# lpcdev.net
KiCad netlist of a schematic drawn in EAGLE
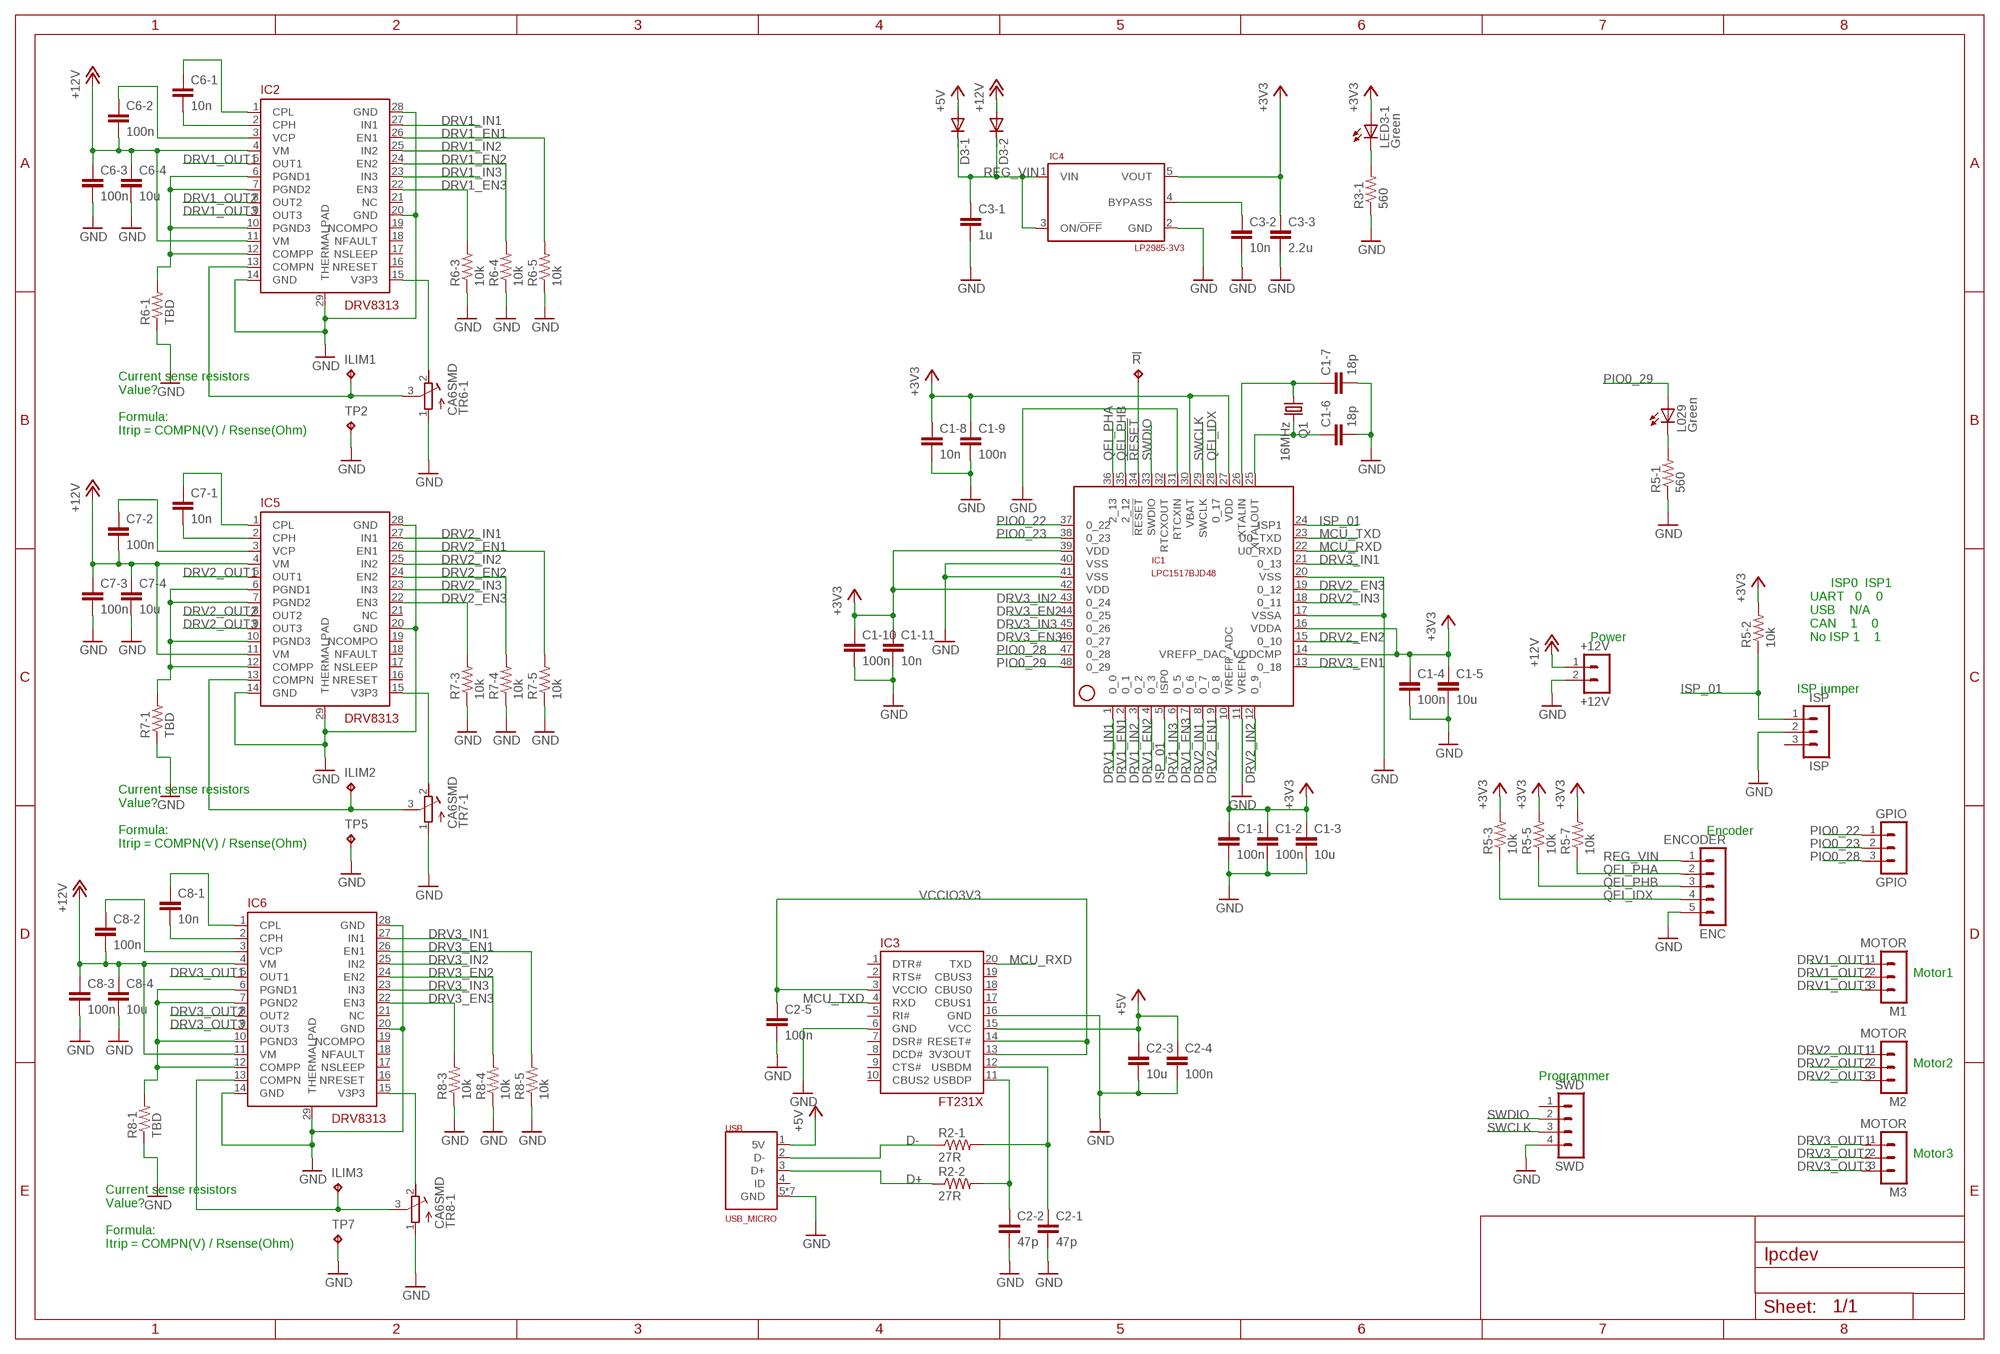
[diagram p0: schematic, sheet 1]

(export (version "E")
  (design (tool "Eeschema 10.0.6"))
  (components
    (comp (ref "!R")
      (value "TPB1,27")
      (footprint "eagle-import:B1,27")
      (libsource (lib "eagle-import") (part "TPB1,27"))
    )
    (comp (ref "+12V")
      (value "+12V")
      (footprint "eagle-import:MA02-1")
      (libsource (lib "eagle-import") (part "MA02-1"))
    )
    (comp (ref "C1-1")
      (value "100n")
      (footprint "eagle-import:C0603")
      (libsource (lib "eagle-import") (part "C-EUC0603"))
    )
    (comp (ref "C1-2")
      (value "100n")
      (footprint "eagle-import:C0603")
      (libsource (lib "eagle-import") (part "C-EUC0603"))
    )
    (comp (ref "C1-3")
      (value "10u")
      (footprint "eagle-import:C0805")
      (libsource (lib "eagle-import") (part "C-EUC0805"))
    )
    (comp (ref "C1-4")
      (value "100n")
      (footprint "eagle-import:C0603")
      (libsource (lib "eagle-import") (part "C-EUC0603"))
    )
    (comp (ref "C1-5")
      (value "10u")
      (footprint "eagle-import:C0805")
      (libsource (lib "eagle-import") (part "C-EUC0805"))
    )
    (comp (ref "C1-6")
      (value "18p")
      (footprint "eagle-import:C0603")
      (libsource (lib "eagle-import") (part "C-EUC0603"))
    )
    (comp (ref "C1-7")
      (value "18p")
      (footprint "eagle-import:C0603")
      (libsource (lib "eagle-import") (part "C-EUC0603"))
    )
    (comp (ref "C1-8")
      (value "10n")
      (footprint "eagle-import:C0603")
      (libsource (lib "eagle-import") (part "C-EUC0603"))
    )
    (comp (ref "C1-9")
      (value "100n")
      (footprint "eagle-import:C0603")
      (libsource (lib "eagle-import") (part "C-EUC0603"))
    )
    (comp (ref "C1-10")
      (value "100n")
      (footprint "eagle-import:C0603")
      (libsource (lib "eagle-import") (part "C-EUC0603"))
    )
    (comp (ref "C1-11")
      (value "10n")
      (footprint "eagle-import:C0603")
      (libsource (lib "eagle-import") (part "C-EUC0603"))
    )
    (comp (ref "C2-1")
      (value "47p")
      (footprint "eagle-import:C0603")
      (libsource (lib "eagle-import") (part "C-EUC0603"))
    )
    (comp (ref "C2-2")
      (value "47p")
      (footprint "eagle-import:C0603")
      (libsource (lib "eagle-import") (part "C-EUC0603"))
    )
    (comp (ref "C2-3")
      (value "10u")
      (footprint "eagle-import:C0805")
      (libsource (lib "eagle-import") (part "C-EUC0805"))
    )
    (comp (ref "C2-4")
      (value "100n")
      (footprint "eagle-import:C0603")
      (libsource (lib "eagle-import") (part "C-EUC0603"))
    )
    (comp (ref "C2-5")
      (value "100n")
      (footprint "eagle-import:C0603")
      (libsource (lib "eagle-import") (part "C-EUC0603"))
    )
    (comp (ref "C3-1")
      (value "1u")
      (footprint "eagle-import:C0805")
      (libsource (lib "eagle-import") (part "C-EUC0805"))
    )
    (comp (ref "C3-2")
      (value "10n")
      (footprint "eagle-import:C0603")
      (libsource (lib "eagle-import") (part "C-EUC0603"))
    )
    (comp (ref "C3-3")
      (value "2.2u")
      (footprint "eagle-import:C0805")
      (libsource (lib "eagle-import") (part "C-EUC0805"))
    )
    (comp (ref "C6-1")
      (value "10n")
      (footprint "eagle-import:C0603")
      (libsource (lib "eagle-import") (part "C-EUC0603"))
    )
    (comp (ref "C6-2")
      (value "100n")
      (footprint "eagle-import:C0603")
      (libsource (lib "eagle-import") (part "C-EUC0603"))
    )
    (comp (ref "C6-3")
      (value "100n")
      (footprint "eagle-import:C0603")
      (libsource (lib "eagle-import") (part "C-EUC0603"))
    )
    (comp (ref "C6-4")
      (value "10u")
      (footprint "eagle-import:C0805")
      (libsource (lib "eagle-import") (part "C-EUC0805"))
    )
    (comp (ref "C7-1")
      (value "10n")
      (footprint "eagle-import:C0603")
      (libsource (lib "eagle-import") (part "C-EUC0603"))
    )
    (comp (ref "C7-2")
      (value "100n")
      (footprint "eagle-import:C0603")
      (libsource (lib "eagle-import") (part "C-EUC0603"))
    )
    (comp (ref "C7-3")
      (value "100n")
      (footprint "eagle-import:C0603")
      (libsource (lib "eagle-import") (part "C-EUC0603"))
    )
    (comp (ref "C7-4")
      (value "10u")
      (footprint "eagle-import:C0805")
      (libsource (lib "eagle-import") (part "C-EUC0805"))
    )
    (comp (ref "C8-1")
      (value "10n")
      (footprint "eagle-import:C0603")
      (libsource (lib "eagle-import") (part "C-EUC0603"))
    )
    (comp (ref "C8-2")
      (value "100n")
      (footprint "eagle-import:C0603")
      (libsource (lib "eagle-import") (part "C-EUC0603"))
    )
    (comp (ref "C8-3")
      (value "100n")
      (footprint "eagle-import:C0603")
      (libsource (lib "eagle-import") (part "C-EUC0603"))
    )
    (comp (ref "C8-4")
      (value "10u")
      (footprint "eagle-import:C0805")
      (libsource (lib "eagle-import") (part "C-EUC0805"))
    )
    (comp (ref "D3-1")
      (value "DIODE-SOD323-R")
      (footprint "eagle-import:SOD323-R")
      (libsource (lib "eagle-import") (part "DIODE-SOD323-R"))
    )
    (comp (ref "D3-2")
      (value "DIODE-SOD323-R")
      (footprint "eagle-import:SOD323-R")
      (libsource (lib "eagle-import") (part "DIODE-SOD323-R"))
    )
    (comp (ref "ENC")
      (value "ENCODER")
      (footprint "eagle-import:MA05-1")
      (libsource (lib "eagle-import") (part "MA05-1"))
    )
    (comp (ref "GPIO")
      (value "GPIO")
      (footprint "eagle-import:MA03-1")
      (libsource (lib "eagle-import") (part "MA03-1"))
    )
    (comp (ref "IC1")
      (value "LPC1517BJD48")
      (footprint "eagle-import:LQFP48")
      (libsource (lib "eagle-import") (part "LPC1517BJD48"))
    )
    (comp (ref "IC2")
      (value "DRV8313")
      (footprint "eagle-import:R-PDSO-G28")
      (libsource (lib "eagle-import") (part "DRV8313"))
    )
    (comp (ref "IC3")
      (value "FT231X")
      (footprint "eagle-import:SSOP-20")
      (libsource (lib "eagle-import") (part "FT231X"))
    )
    (comp (ref "IC4")
      (value "LP2985-3V3")
      (footprint "eagle-import:SOT23")
      (libsource (lib "eagle-import") (part "LP2985-3V3"))
    )
    (comp (ref "IC5")
      (value "DRV8313")
      (footprint "eagle-import:R-PDSO-G28")
      (libsource (lib "eagle-import") (part "DRV8313"))
    )
    (comp (ref "IC6")
      (value "DRV8313")
      (footprint "eagle-import:R-PDSO-G28")
      (libsource (lib "eagle-import") (part "DRV8313"))
    )
    (comp (ref "ILIM1")
      (value "TPB1,27")
      (footprint "eagle-import:B1,27")
      (libsource (lib "eagle-import") (part "TPB1,27"))
    )
    (comp (ref "ILIM2")
      (value "TPB1,27")
      (footprint "eagle-import:B1,27")
      (libsource (lib "eagle-import") (part "TPB1,27"))
    )
    (comp (ref "ILIM3")
      (value "TPB1,27")
      (footprint "eagle-import:B1,27")
      (libsource (lib "eagle-import") (part "TPB1,27"))
    )
    (comp (ref "ISP")
      (value "ISP")
      (footprint "eagle-import:MA03-1")
      (libsource (lib "eagle-import") (part "MA03-1"))
    )
    (comp (ref "L029")
      (value "Green")
      (footprint "eagle-import:CHIP-LED0603")
      (libsource (lib "eagle-import") (part "LEDCHIP-LED0603"))
    )
    (comp (ref "LED3-1")
      (value "Green")
      (footprint "eagle-import:CHIP-LED0603")
      (libsource (lib "eagle-import") (part "LEDCHIP-LED0603"))
    )
    (comp (ref "M1")
      (value "MOTOR")
      (footprint "eagle-import:MA03-1")
      (libsource (lib "eagle-import") (part "MA03-1"))
    )
    (comp (ref "M2")
      (value "MOTOR")
      (footprint "eagle-import:MA03-1")
      (libsource (lib "eagle-import") (part "MA03-1"))
    )
    (comp (ref "M3")
      (value "MOTOR")
      (footprint "eagle-import:MA03-1")
      (libsource (lib "eagle-import") (part "MA03-1"))
    )
    (comp (ref "Q1")
      (value "16MHz")
      (footprint "eagle-import:CTS406")
      (libsource (lib "eagle-import") (part "CRYSTALCTS406"))
    )
    (comp (ref "R2-1")
      (value "27R")
      (footprint "eagle-import:R0603")
      (libsource (lib "eagle-import") (part "R-US_R0603"))
    )
    (comp (ref "R2-2")
      (value "27R")
      (footprint "eagle-import:R0603")
      (libsource (lib "eagle-import") (part "R-US_R0603"))
    )
    (comp (ref "R3-1")
      (value "560")
      (footprint "eagle-import:R0603")
      (libsource (lib "eagle-import") (part "R-US_R0603"))
    )
    (comp (ref "R5-1")
      (value "560")
      (footprint "eagle-import:R0603")
      (libsource (lib "eagle-import") (part "R-US_R0603"))
    )
    (comp (ref "R5-2")
      (value "10k")
      (footprint "eagle-import:R0603")
      (libsource (lib "eagle-import") (part "R-US_R0603"))
    )
    (comp (ref "R5-3")
      (value "10k")
      (footprint "eagle-import:R0603")
      (libsource (lib "eagle-import") (part "R-US_R0603"))
    )
    (comp (ref "R5-5")
      (value "10k")
      (footprint "eagle-import:R0603")
      (libsource (lib "eagle-import") (part "R-US_R0603"))
    )
    (comp (ref "R5-7")
      (value "10k")
      (footprint "eagle-import:R0603")
      (libsource (lib "eagle-import") (part "R-US_R0603"))
    )
    (comp (ref "R6-1")
      (value "TBD")
      (footprint "eagle-import:R0805")
      (libsource (lib "eagle-import") (part "R-US_R0805"))
    )
    (comp (ref "R6-3")
      (value "10k")
      (footprint "eagle-import:R0603")
      (libsource (lib "eagle-import") (part "R-US_R0603"))
    )
    (comp (ref "R6-4")
      (value "10k")
      (footprint "eagle-import:R0603")
      (libsource (lib "eagle-import") (part "R-US_R0603"))
    )
    (comp (ref "R6-5")
      (value "10k")
      (footprint "eagle-import:R0603")
      (libsource (lib "eagle-import") (part "R-US_R0603"))
    )
    (comp (ref "R7-1")
      (value "TBD")
      (footprint "eagle-import:R0805")
      (libsource (lib "eagle-import") (part "R-US_R0805"))
    )
    (comp (ref "R7-3")
      (value "10k")
      (footprint "eagle-import:R0603")
      (libsource (lib "eagle-import") (part "R-US_R0603"))
    )
    (comp (ref "R7-4")
      (value "10k")
      (footprint "eagle-import:R0603")
      (libsource (lib "eagle-import") (part "R-US_R0603"))
    )
    (comp (ref "R7-5")
      (value "10k")
      (footprint "eagle-import:R0603")
      (libsource (lib "eagle-import") (part "R-US_R0603"))
    )
    (comp (ref "R8-1")
      (value "TBD")
      (footprint "eagle-import:R0805")
      (libsource (lib "eagle-import") (part "R-US_R0805"))
    )
    (comp (ref "R8-3")
      (value "10k")
      (footprint "eagle-import:R0603")
      (libsource (lib "eagle-import") (part "R-US_R0603"))
    )
    (comp (ref "R8-4")
      (value "10k")
      (footprint "eagle-import:R0603")
      (libsource (lib "eagle-import") (part "R-US_R0603"))
    )
    (comp (ref "R8-5")
      (value "10k")
      (footprint "eagle-import:R0603")
      (libsource (lib "eagle-import") (part "R-US_R0603"))
    )
    (comp (ref "SWD")
      (value "SWD")
      (footprint "eagle-import:MA04-1")
      (libsource (lib "eagle-import") (part "MA04-1"))
    )
    (comp (ref "TP2")
      (value "TPB1,27")
      (footprint "eagle-import:B1,27")
      (libsource (lib "eagle-import") (part "TPB1,27"))
    )
    (comp (ref "TP5")
      (value "TPB1,27")
      (footprint "eagle-import:B1,27")
      (libsource (lib "eagle-import") (part "TPB1,27"))
    )
    (comp (ref "TP7")
      (value "TPB1,27")
      (footprint "eagle-import:B1,27")
      (libsource (lib "eagle-import") (part "TPB1,27"))
    )
    (comp (ref "TR6-1")
      (value "CA6SMD")
      (footprint "eagle-import:CA6SMD")
      (libsource (lib "eagle-import") (part "CA6SMD"))
    )
    (comp (ref "TR7-1")
      (value "CA6SMD")
      (footprint "eagle-import:CA6SMD")
      (libsource (lib "eagle-import") (part "CA6SMD"))
    )
    (comp (ref "TR8-1")
      (value "CA6SMD")
      (footprint "eagle-import:CA6SMD")
      (libsource (lib "eagle-import") (part "CA6SMD"))
    )
    (comp (ref "USB")
      (value "USB_MICRO")
      (footprint "eagle-import:USB_MICRO")
      (libsource (lib "eagle-import") (part "USB_MICRO"))
    )
  )
  (nets
    (net (code "1") (name "+3V3") (class "Default")
      (node (ref "C1-1") (pin "1") (pinfunction "1_1") (pintype "passive"))
      (node (ref "C1-10") (pin "1") (pinfunction "1_1") (pintype "passive"))
      (node (ref "C1-11") (pin "1") (pinfunction "1_1") (pintype "passive"))
      (node (ref "C1-2") (pin "1") (pinfunction "1_1") (pintype "passive"))
      (node (ref "C1-3") (pin "1") (pinfunction "1_1") (pintype "passive"))
      (node (ref "C1-4") (pin "1") (pinfunction "1_1") (pintype "passive"))
      (node (ref "C1-5") (pin "1") (pinfunction "1_1") (pintype "passive"))
      (node (ref "C1-8") (pin "1") (pinfunction "1_1") (pintype "passive"))
      (node (ref "C1-9") (pin "1") (pinfunction "1_1") (pintype "passive"))
      (node (ref "C3-3") (pin "1") (pinfunction "1_1") (pintype "passive"))
      (node (ref "IC1") (pin "10") (pinfunction "VREFP_ADC_10") (pintype "power_in"))
      (node (ref "IC1") (pin "14") (pinfunction "VREFP_DAC_VDDCMP_14") (pintype "power_in"))
      (node (ref "IC1") (pin "16") (pinfunction "VDDA_16") (pintype "power_in"))
      (node (ref "IC1") (pin "27") (pinfunction "VDD_27") (pintype "power_in"))
      (node (ref "IC1") (pin "30") (pinfunction "VBAT_30") (pintype "power_in"))
      (node (ref "IC1") (pin "39") (pinfunction "VDD_39") (pintype "power_in"))
      (node (ref "IC1") (pin "42") (pinfunction "VDD_42") (pintype "power_in"))
      (node (ref "IC4") (pin "5") (pinfunction "VOUT_5") (pintype "bidirectional"))
      (node (ref "LED3-1") (pin "A") (pinfunction "A_A") (pintype "passive"))
      (node (ref "R5-2") (pin "2") (pinfunction "2_2") (pintype "passive"))
      (node (ref "R5-3") (pin "2") (pinfunction "2_2") (pintype "passive"))
      (node (ref "R5-5") (pin "2") (pinfunction "2_2") (pintype "passive"))
      (node (ref "R5-7") (pin "2") (pinfunction "2_2") (pintype "passive"))
    )
    (net (code "2") (name "+5V") (class "Default")
      (node (ref "C2-3") (pin "1") (pinfunction "1_1") (pintype "passive"))
      (node (ref "C2-4") (pin "1") (pinfunction "1_1") (pintype "passive"))
      (node (ref "D3-1") (pin "A") (pinfunction "A_A") (pintype "passive"))
      (node (ref "IC3") (pin "15") (pinfunction "VCC_15") (pintype "power_in"))
      (node (ref "USB") (pin "1") (pinfunction "5V_1") (pintype "bidirectional"))
    )
    (net (code "3") (name "+12V") (class "Default")
      (node (ref "+12V") (pin "1") (pinfunction "1_1") (pintype "passive"))
      (node (ref "C6-2") (pin "2") (pinfunction "2_2") (pintype "passive"))
      (node (ref "C6-3") (pin "1") (pinfunction "1_1") (pintype "passive"))
      (node (ref "C6-4") (pin "1") (pinfunction "1_1") (pintype "passive"))
      (node (ref "C7-2") (pin "2") (pinfunction "2_2") (pintype "passive"))
      (node (ref "C7-3") (pin "1") (pinfunction "1_1") (pintype "passive"))
      (node (ref "C7-4") (pin "1") (pinfunction "1_1") (pintype "passive"))
      (node (ref "C8-2") (pin "2") (pinfunction "2_2") (pintype "passive"))
      (node (ref "C8-3") (pin "1") (pinfunction "1_1") (pintype "passive"))
      (node (ref "C8-4") (pin "1") (pinfunction "1_1") (pintype "passive"))
      (node (ref "D3-2") (pin "A") (pinfunction "A_A") (pintype "passive"))
      (node (ref "IC2") (pin "11") (pinfunction "VM_11") (pintype "power_in"))
      (node (ref "IC2") (pin "4") (pinfunction "VM_4") (pintype "power_in"))
      (node (ref "IC5") (pin "11") (pinfunction "VM_11") (pintype "power_in"))
      (node (ref "IC5") (pin "4") (pinfunction "VM_4") (pintype "power_in"))
      (node (ref "IC6") (pin "11") (pinfunction "VM_11") (pintype "power_in"))
      (node (ref "IC6") (pin "4") (pinfunction "VM_4") (pintype "power_in"))
    )
    (net (code "4") (name "/D+") (class "Default")
      (node (ref "R2-2") (pin "1") (pinfunction "1_1") (pintype "passive"))
      (node (ref "USB") (pin "3") (pinfunction "D+_3") (pintype "bidirectional"))
    )
    (net (code "5") (name "/D-") (class "Default")
      (node (ref "R2-1") (pin "1") (pinfunction "1_1") (pintype "passive"))
      (node (ref "USB") (pin "2") (pinfunction "D-_2") (pintype "bidirectional"))
    )
    (net (code "6") (name "/DRV1_EN1") (class "Default")
      (node (ref "IC1") (pin "2") (pinfunction "0_1_2") (pintype "bidirectional"))
      (node (ref "IC2") (pin "26") (pinfunction "EN1_26") (pintype "input"))
      (node (ref "R6-5") (pin "2") (pinfunction "2_2") (pintype "passive"))
    )
    (net (code "7") (name "/DRV1_EN2") (class "Default")
      (node (ref "IC1") (pin "4") (pinfunction "0_3_4") (pintype "bidirectional"))
      (node (ref "IC2") (pin "24") (pinfunction "EN2_24") (pintype "input"))
      (node (ref "R6-4") (pin "2") (pinfunction "2_2") (pintype "passive"))
    )
    (net (code "8") (name "/DRV1_EN3") (class "Default")
      (node (ref "IC1") (pin "7") (pinfunction "0_6_7") (pintype "bidirectional"))
      (node (ref "IC2") (pin "22") (pinfunction "EN3_22") (pintype "input"))
      (node (ref "R6-3") (pin "2") (pinfunction "2_2") (pintype "passive"))
    )
    (net (code "9") (name "/DRV1_IN1") (class "Default")
      (node (ref "IC1") (pin "1") (pinfunction "0_0_1") (pintype "bidirectional"))
      (node (ref "IC2") (pin "27") (pinfunction "IN1_27") (pintype "input"))
    )
    (net (code "10") (name "/DRV1_IN2") (class "Default")
      (node (ref "IC1") (pin "3") (pinfunction "0_2_3") (pintype "bidirectional"))
      (node (ref "IC2") (pin "25") (pinfunction "IN2_25") (pintype "input"))
    )
    (net (code "11") (name "/DRV1_IN3") (class "Default")
      (node (ref "IC1") (pin "6") (pinfunction "0_5_6") (pintype "bidirectional"))
      (node (ref "IC2") (pin "23") (pinfunction "IN3_23") (pintype "input"))
    )
    (net (code "12") (name "/DRV1_OUT1") (class "Default")
      (node (ref "IC2") (pin "5") (pinfunction "OUT1_5") (pintype "output"))
      (node (ref "M1") (pin "1") (pinfunction "1_1") (pintype "passive"))
    )
    (net (code "13") (name "/DRV1_OUT2") (class "Default")
      (node (ref "IC2") (pin "8") (pinfunction "OUT2_8") (pintype "output"))
      (node (ref "M1") (pin "2") (pinfunction "2_2") (pintype "passive"))
    )
    (net (code "14") (name "/DRV1_OUT3") (class "Default")
      (node (ref "IC2") (pin "9") (pinfunction "OUT3_9") (pintype "output"))
      (node (ref "M1") (pin "3") (pinfunction "3_3") (pintype "passive"))
    )
    (net (code "15") (name "/DRV2_EN1") (class "Default")
      (node (ref "IC1") (pin "9") (pinfunction "0_8_9") (pintype "bidirectional"))
      (node (ref "IC5") (pin "26") (pinfunction "EN1_26") (pintype "input"))
      (node (ref "R7-5") (pin "2") (pinfunction "2_2") (pintype "passive"))
    )
    (net (code "16") (name "/DRV2_EN2") (class "Default")
      (node (ref "IC1") (pin "15") (pinfunction "0_10_15") (pintype "bidirectional"))
      (node (ref "IC5") (pin "24") (pinfunction "EN2_24") (pintype "input"))
      (node (ref "R7-4") (pin "2") (pinfunction "2_2") (pintype "passive"))
    )
    (net (code "17") (name "/DRV2_EN3") (class "Default")
      (node (ref "IC1") (pin "19") (pinfunction "0_12_19") (pintype "bidirectional"))
      (node (ref "IC5") (pin "22") (pinfunction "EN3_22") (pintype "input"))
      (node (ref "R7-3") (pin "2") (pinfunction "2_2") (pintype "passive"))
    )
    (net (code "18") (name "/DRV2_IN1") (class "Default")
      (node (ref "IC1") (pin "8") (pinfunction "0_7_8") (pintype "bidirectional"))
      (node (ref "IC5") (pin "27") (pinfunction "IN1_27") (pintype "input"))
    )
    (net (code "19") (name "/DRV2_IN2") (class "Default")
      (node (ref "IC1") (pin "12") (pinfunction "0_9_12") (pintype "bidirectional"))
      (node (ref "IC5") (pin "25") (pinfunction "IN2_25") (pintype "input"))
    )
    (net (code "20") (name "/DRV2_IN3") (class "Default")
      (node (ref "IC1") (pin "18") (pinfunction "0_11_18") (pintype "bidirectional"))
      (node (ref "IC5") (pin "23") (pinfunction "IN3_23") (pintype "input"))
    )
    (net (code "21") (name "/DRV2_OUT1") (class "Default")
      (node (ref "IC5") (pin "5") (pinfunction "OUT1_5") (pintype "output"))
      (node (ref "M2") (pin "1") (pinfunction "1_1") (pintype "passive"))
    )
    (net (code "22") (name "/DRV2_OUT2") (class "Default")
      (node (ref "IC5") (pin "8") (pinfunction "OUT2_8") (pintype "output"))
      (node (ref "M2") (pin "2") (pinfunction "2_2") (pintype "passive"))
    )
    (net (code "23") (name "/DRV2_OUT3") (class "Default")
      (node (ref "IC5") (pin "9") (pinfunction "OUT3_9") (pintype "output"))
      (node (ref "M2") (pin "3") (pinfunction "3_3") (pintype "passive"))
    )
    (net (code "24") (name "/DRV3_EN1") (class "Default")
      (node (ref "IC1") (pin "13") (pinfunction "0_18_13") (pintype "bidirectional"))
      (node (ref "IC6") (pin "26") (pinfunction "EN1_26") (pintype "input"))
      (node (ref "R8-5") (pin "2") (pinfunction "2_2") (pintype "passive"))
    )
    (net (code "25") (name "/DRV3_EN2") (class "Default")
      (node (ref "IC1") (pin "44") (pinfunction "0_25_44") (pintype "bidirectional"))
      (node (ref "IC6") (pin "24") (pinfunction "EN2_24") (pintype "input"))
      (node (ref "R8-4") (pin "2") (pinfunction "2_2") (pintype "passive"))
    )
    (net (code "26") (name "/DRV3_EN3") (class "Default")
      (node (ref "IC1") (pin "46") (pinfunction "0_27_46") (pintype "bidirectional"))
      (node (ref "IC6") (pin "22") (pinfunction "EN3_22") (pintype "input"))
      (node (ref "R8-3") (pin "2") (pinfunction "2_2") (pintype "passive"))
    )
    (net (code "27") (name "/DRV3_IN1") (class "Default")
      (node (ref "IC1") (pin "21") (pinfunction "0_13_21") (pintype "bidirectional"))
      (node (ref "IC6") (pin "27") (pinfunction "IN1_27") (pintype "input"))
    )
    (net (code "28") (name "/DRV3_IN2") (class "Default")
      (node (ref "IC1") (pin "43") (pinfunction "0_24_43") (pintype "bidirectional"))
      (node (ref "IC6") (pin "25") (pinfunction "IN2_25") (pintype "input"))
    )
    (net (code "29") (name "/DRV3_IN3") (class "Default")
      (node (ref "IC1") (pin "45") (pinfunction "0_26_45") (pintype "bidirectional"))
      (node (ref "IC6") (pin "23") (pinfunction "IN3_23") (pintype "input"))
    )
    (net (code "30") (name "/DRV3_OUT1") (class "Default")
      (node (ref "IC6") (pin "5") (pinfunction "OUT1_5") (pintype "output"))
      (node (ref "M3") (pin "1") (pinfunction "1_1") (pintype "passive"))
    )
    (net (code "31") (name "/DRV3_OUT2") (class "Default")
      (node (ref "IC6") (pin "8") (pinfunction "OUT2_8") (pintype "output"))
      (node (ref "M3") (pin "2") (pinfunction "2_2") (pintype "passive"))
    )
    (net (code "32") (name "/DRV3_OUT3") (class "Default")
      (node (ref "IC6") (pin "9") (pinfunction "OUT3_9") (pintype "output"))
      (node (ref "M3") (pin "3") (pinfunction "3_3") (pintype "passive"))
    )
    (net (code "33") (name "/ISP_01") (class "Default")
      (node (ref "IC1") (pin "24") (pinfunction "ISP1_24") (pintype "bidirectional"))
      (node (ref "IC1") (pin "5") (pinfunction "ISP0_5") (pintype "bidirectional"))
      (node (ref "ISP") (pin "1") (pinfunction "1_1") (pintype "passive"))
      (node (ref "R5-2") (pin "1") (pinfunction "1_1") (pintype "passive"))
    )
    (net (code "34") (name "/MCU_RXD") (class "Default")
      (node (ref "IC1") (pin "22") (pinfunction "U0_RXD_22") (pintype "bidirectional"))
      (node (ref "IC3") (pin "20") (pinfunction "TXD_20") (pintype "bidirectional"))
    )
    (net (code "35") (name "/MCU_TXD") (class "Default")
      (node (ref "IC1") (pin "23") (pinfunction "U0_TXD_23") (pintype "bidirectional"))
      (node (ref "IC3") (pin "4") (pinfunction "RXD_4") (pintype "input"))
    )
    (net (code "36") (name "/PIO0_22") (class "Default")
      (node (ref "GPIO") (pin "1") (pinfunction "1_1") (pintype "passive"))
      (node (ref "IC1") (pin "37") (pinfunction "0_22_37") (pintype "bidirectional"))
    )
    (net (code "37") (name "/PIO0_23") (class "Default")
      (node (ref "GPIO") (pin "2") (pinfunction "2_2") (pintype "passive"))
      (node (ref "IC1") (pin "38") (pinfunction "0_23_38") (pintype "bidirectional"))
    )
    (net (code "38") (name "/PIO0_28") (class "Default")
      (node (ref "GPIO") (pin "3") (pinfunction "3_3") (pintype "passive"))
      (node (ref "IC1") (pin "47") (pinfunction "0_28_47") (pintype "bidirectional"))
    )
    (net (code "39") (name "/PIO0_29") (class "Default")
      (node (ref "IC1") (pin "48") (pinfunction "0_29_48") (pintype "bidirectional"))
      (node (ref "L029") (pin "A") (pinfunction "A_A") (pintype "passive"))
    )
    (net (code "40") (name "/QEI_IDX") (class "Default")
      (node (ref "ENC") (pin "4") (pinfunction "4_4") (pintype "passive"))
      (node (ref "IC1") (pin "28") (pinfunction "0_17_28") (pintype "bidirectional"))
      (node (ref "R5-3") (pin "1") (pinfunction "1_1") (pintype "passive"))
    )
    (net (code "41") (name "/QEI_PHA") (class "Default")
      (node (ref "ENC") (pin "2") (pinfunction "2_2") (pintype "passive"))
      (node (ref "IC1") (pin "36") (pinfunction "2_13_36") (pintype "bidirectional"))
      (node (ref "R5-7") (pin "1") (pinfunction "1_1") (pintype "passive"))
    )
    (net (code "42") (name "/QEI_PHB") (class "Default")
      (node (ref "ENC") (pin "3") (pinfunction "3_3") (pintype "passive"))
      (node (ref "IC1") (pin "35") (pinfunction "2_12_35") (pintype "bidirectional"))
      (node (ref "R5-5") (pin "1") (pinfunction "1_1") (pintype "passive"))
    )
    (net (code "43") (name "/REG_VIN") (class "Default")
      (node (ref "C3-1") (pin "1") (pinfunction "1_1") (pintype "passive"))
      (node (ref "D3-1") (pin "C") (pinfunction "C_C") (pintype "passive"))
      (node (ref "D3-2") (pin "C") (pinfunction "C_C") (pintype "passive"))
      (node (ref "ENC") (pin "1") (pinfunction "1_1") (pintype "passive"))
      (node (ref "IC4") (pin "1") (pinfunction "VIN_1") (pintype "bidirectional"))
      (node (ref "IC4") (pin "3") (pinfunction "ON/~{OFF}_3") (pintype "bidirectional"))
    )
    (net (code "44") (name "/SWCLK") (class "Default")
      (node (ref "IC1") (pin "29") (pinfunction "SWCLK_29") (pintype "bidirectional"))
      (node (ref "SWD") (pin "3") (pinfunction "3_3") (pintype "passive"))
    )
    (net (code "45") (name "/SWDIO") (class "Default")
      (node (ref "IC1") (pin "33") (pinfunction "SWDIO_33") (pintype "bidirectional"))
      (node (ref "SWD") (pin "2") (pinfunction "2_2") (pintype "passive"))
    )
    (net (code "46") (name "/VCCIO3V3") (class "Default")
      (node (ref "C2-5") (pin "1") (pinfunction "1_1") (pintype "passive"))
      (node (ref "IC3") (pin "13") (pinfunction "3V3OUT_13") (pintype "power_in"))
      (node (ref "IC3") (pin "14") (pinfunction "RESET#_14") (pintype "input"))
      (node (ref "IC3") (pin "3") (pinfunction "VCCIO_3") (pintype "power_in"))
    )
    (net (code "47") (name "/~{RESET}") (class "Default")
      (node (ref "!R") (pin "TP") (pinfunction "TP_TP") (pintype "input"))
      (node (ref "IC1") (pin "34") (pinfunction "~{RESET}_34") (pintype "bidirectional"))
    )
    (net (code "48") (name "GND") (class "Default")
      (node (ref "+12V") (pin "2") (pinfunction "2_2") (pintype "passive"))
      (node (ref "C1-1") (pin "2") (pinfunction "2_2") (pintype "passive"))
      (node (ref "C1-10") (pin "2") (pinfunction "2_2") (pintype "passive"))
      (node (ref "C1-11") (pin "2") (pinfunction "2_2") (pintype "passive"))
      (node (ref "C1-2") (pin "2") (pinfunction "2_2") (pintype "passive"))
      (node (ref "C1-3") (pin "2") (pinfunction "2_2") (pintype "passive"))
      (node (ref "C1-4") (pin "2") (pinfunction "2_2") (pintype "passive"))
      (node (ref "C1-5") (pin "2") (pinfunction "2_2") (pintype "passive"))
      (node (ref "C1-6") (pin "2") (pinfunction "2_2") (pintype "passive"))
      (node (ref "C1-7") (pin "2") (pinfunction "2_2") (pintype "passive"))
      (node (ref "C1-8") (pin "2") (pinfunction "2_2") (pintype "passive"))
      (node (ref "C1-9") (pin "2") (pinfunction "2_2") (pintype "passive"))
      (node (ref "C2-1") (pin "2") (pinfunction "2_2") (pintype "passive"))
      (node (ref "C2-2") (pin "2") (pinfunction "2_2") (pintype "passive"))
      (node (ref "C2-3") (pin "2") (pinfunction "2_2") (pintype "passive"))
      (node (ref "C2-4") (pin "2") (pinfunction "2_2") (pintype "passive"))
      (node (ref "C2-5") (pin "2") (pinfunction "2_2") (pintype "passive"))
      (node (ref "C3-1") (pin "2") (pinfunction "2_2") (pintype "passive"))
      (node (ref "C3-2") (pin "2") (pinfunction "2_2") (pintype "passive"))
      (node (ref "C3-3") (pin "2") (pinfunction "2_2") (pintype "passive"))
      (node (ref "C6-3") (pin "2") (pinfunction "2_2") (pintype "passive"))
      (node (ref "C6-4") (pin "2") (pinfunction "2_2") (pintype "passive"))
      (node (ref "C7-3") (pin "2") (pinfunction "2_2") (pintype "passive"))
      (node (ref "C7-4") (pin "2") (pinfunction "2_2") (pintype "passive"))
      (node (ref "C8-3") (pin "2") (pinfunction "2_2") (pintype "passive"))
      (node (ref "C8-4") (pin "2") (pinfunction "2_2") (pintype "passive"))
      (node (ref "ENC") (pin "5") (pinfunction "5_5") (pintype "passive"))
      (node (ref "IC1") (pin "11") (pinfunction "VREFN_11") (pintype "power_in"))
      (node (ref "IC1") (pin "17") (pinfunction "VSSA_17") (pintype "power_in"))
      (node (ref "IC1") (pin "20") (pinfunction "VSS_20") (pintype "power_in"))
      (node (ref "IC1") (pin "31") (pinfunction "RTCXIN_31") (pintype "bidirectional"))
      (node (ref "IC1") (pin "40") (pinfunction "VSS_40") (pintype "power_in"))
      (node (ref "IC1") (pin "41") (pinfunction "VSS_41") (pintype "power_in"))
      (node (ref "IC2") (pin "14") (pinfunction "GND_14") (pintype "power_in"))
      (node (ref "IC2") (pin "20") (pinfunction "GND_20") (pintype "power_in"))
      (node (ref "IC2") (pin "28") (pinfunction "GND_28") (pintype "power_in"))
      (node (ref "IC2") (pin "29") (pinfunction "THERMALPAD_29") (pintype "power_in"))
      (node (ref "IC3") (pin "16") (pinfunction "GND_16") (pintype "power_in"))
      (node (ref "IC3") (pin "6") (pinfunction "GND_6") (pintype "power_in"))
      (node (ref "IC4") (pin "2") (pinfunction "GND_2") (pintype "bidirectional"))
      (node (ref "IC5") (pin "14") (pinfunction "GND_14") (pintype "power_in"))
      (node (ref "IC5") (pin "20") (pinfunction "GND_20") (pintype "power_in"))
      (node (ref "IC5") (pin "28") (pinfunction "GND_28") (pintype "power_in"))
      (node (ref "IC5") (pin "29") (pinfunction "THERMALPAD_29") (pintype "power_in"))
      (node (ref "IC6") (pin "14") (pinfunction "GND_14") (pintype "power_in"))
      (node (ref "IC6") (pin "20") (pinfunction "GND_20") (pintype "power_in"))
      (node (ref "IC6") (pin "28") (pinfunction "GND_28") (pintype "power_in"))
      (node (ref "IC6") (pin "29") (pinfunction "THERMALPAD_29") (pintype "power_in"))
      (node (ref "ISP") (pin "2") (pinfunction "2_2") (pintype "passive"))
      (node (ref "R3-1") (pin "1") (pinfunction "1_1") (pintype "passive"))
      (node (ref "R5-1") (pin "1") (pinfunction "1_1") (pintype "passive"))
      (node (ref "R6-1") (pin "1") (pinfunction "1_1") (pintype "passive"))
      (node (ref "R6-3") (pin "1") (pinfunction "1_1") (pintype "passive"))
      (node (ref "R6-4") (pin "1") (pinfunction "1_1") (pintype "passive"))
      (node (ref "R6-5") (pin "1") (pinfunction "1_1") (pintype "passive"))
      (node (ref "R7-1") (pin "1") (pinfunction "1_1") (pintype "passive"))
      (node (ref "R7-3") (pin "1") (pinfunction "1_1") (pintype "passive"))
      (node (ref "R7-4") (pin "1") (pinfunction "1_1") (pintype "passive"))
      (node (ref "R7-5") (pin "1") (pinfunction "1_1") (pintype "passive"))
      (node (ref "R8-1") (pin "1") (pinfunction "1_1") (pintype "passive"))
      (node (ref "R8-3") (pin "1") (pinfunction "1_1") (pintype "passive"))
      (node (ref "R8-4") (pin "1") (pinfunction "1_1") (pintype "passive"))
      (node (ref "R8-5") (pin "1") (pinfunction "1_1") (pintype "passive"))
      (node (ref "SWD") (pin "4") (pinfunction "4_4") (pintype "passive"))
      (node (ref "TP2") (pin "TP") (pinfunction "TP_TP") (pintype "input"))
      (node (ref "TP5") (pin "TP") (pinfunction "TP_TP") (pintype "input"))
      (node (ref "TP7") (pin "TP") (pinfunction "TP_TP") (pintype "input"))
      (node (ref "TR6-1") (pin "1") (pinfunction "A_1") (pintype "passive"))
      (node (ref "TR7-1") (pin "1") (pinfunction "A_1") (pintype "passive"))
      (node (ref "TR8-1") (pin "1") (pinfunction "A_1") (pintype "passive"))
      (node (ref "USB") (pin "5") (pinfunction "GND_5") (pintype "bidirectional"))
      (node (ref "USB") (pin "H1") (pinfunction "GND_H1") (pintype "bidirectional"))
      (node (ref "USB") (pin "H2") (pinfunction "GND_H2") (pintype "bidirectional"))
      (node (ref "USB") (pin "S1") (pinfunction "GND_S1") (pintype "bidirectional"))
      (node (ref "USB") (pin "S2") (pinfunction "GND_S2") (pintype "bidirectional"))
      (node (ref "USB") (pin "S3") (pinfunction "GND_S3") (pintype "bidirectional"))
      (node (ref "USB") (pin "S4") (pinfunction "GND_S4") (pintype "bidirectional"))
    )
    (net (code "49") (name "Net-(IC1-XTALIN)") (class "Default")
      (node (ref "C1-7") (pin "1") (pinfunction "1_1") (pintype "passive"))
      (node (ref "IC1") (pin "26") (pinfunction "XTALIN_26") (pintype "bidirectional"))
      (node (ref "Q1") (pin "1") (pinfunction "1_1") (pintype "passive"))
    )
    (net (code "50") (name "Net-(IC1-XTALOUT)") (class "Default")
      (node (ref "C1-6") (pin "1") (pinfunction "1_1") (pintype "passive"))
      (node (ref "IC1") (pin "25") (pinfunction "XTALOUT_25") (pintype "bidirectional"))
      (node (ref "Q1") (pin "3") (pinfunction "2_3") (pintype "passive"))
    )
    (net (code "51") (name "Net-(IC2-COMPN)") (class "Default")
      (node (ref "IC2") (pin "13") (pinfunction "COMPN_13") (pintype "input"))
      (node (ref "ILIM1") (pin "TP") (pinfunction "TP_TP") (pintype "input"))
      (node (ref "TR6-1") (pin "3") (pinfunction "S_3") (pintype "passive"))
    )
    (net (code "52") (name "Net-(IC2-COMPP)") (class "Default")
      (node (ref "IC2") (pin "10") (pinfunction "PGND3_10") (pintype "power_in"))
      (node (ref "IC2") (pin "12") (pinfunction "COMPP_12") (pintype "input"))
      (node (ref "IC2") (pin "6") (pinfunction "PGND1_6") (pintype "power_in"))
      (node (ref "IC2") (pin "7") (pinfunction "PGND2_7") (pintype "power_in"))
      (node (ref "R6-1") (pin "2") (pinfunction "2_2") (pintype "passive"))
    )
    (net (code "53") (name "Net-(IC2-CPH)") (class "Default")
      (node (ref "C6-1") (pin "2") (pinfunction "2_2") (pintype "passive"))
      (node (ref "IC2") (pin "2") (pinfunction "CPH_2") (pintype "power_in"))
    )
    (net (code "54") (name "Net-(IC2-CPL)") (class "Default")
      (node (ref "C6-1") (pin "1") (pinfunction "1_1") (pintype "passive"))
      (node (ref "IC2") (pin "1") (pinfunction "CPL_1") (pintype "power_in"))
    )
    (net (code "55") (name "Net-(IC2-V3P3)") (class "Default")
      (node (ref "IC2") (pin "15") (pinfunction "V3P3_15") (pintype "power_in"))
      (node (ref "TR6-1") (pin "2") (pinfunction "E_2") (pintype "passive"))
    )
    (net (code "56") (name "Net-(IC2-VCP)") (class "Default")
      (node (ref "C6-2") (pin "1") (pinfunction "1_1") (pintype "passive"))
      (node (ref "IC2") (pin "3") (pinfunction "VCP_3") (pintype "power_in"))
    )
    (net (code "57") (name "Net-(IC3-USBDM)") (class "Default")
      (node (ref "C2-1") (pin "1") (pinfunction "1_1") (pintype "passive"))
      (node (ref "IC3") (pin "12") (pinfunction "USBDM_12") (pintype "input"))
      (node (ref "R2-1") (pin "2") (pinfunction "2_2") (pintype "passive"))
    )
    (net (code "58") (name "Net-(IC3-USBDP)") (class "Default")
      (node (ref "C2-2") (pin "1") (pinfunction "1_1") (pintype "passive"))
      (node (ref "IC3") (pin "11") (pinfunction "USBDP_11") (pintype "input"))
      (node (ref "R2-2") (pin "2") (pinfunction "2_2") (pintype "passive"))
    )
    (net (code "59") (name "Net-(IC4-BYPASS)") (class "Default")
      (node (ref "C3-2") (pin "1") (pinfunction "1_1") (pintype "passive"))
      (node (ref "IC4") (pin "4") (pinfunction "BYPASS_4") (pintype "bidirectional"))
    )
    (net (code "60") (name "Net-(IC5-COMPN)") (class "Default")
      (node (ref "IC5") (pin "13") (pinfunction "COMPN_13") (pintype "input"))
      (node (ref "ILIM2") (pin "TP") (pinfunction "TP_TP") (pintype "input"))
      (node (ref "TR7-1") (pin "3") (pinfunction "S_3") (pintype "passive"))
    )
    (net (code "61") (name "Net-(IC5-COMPP)") (class "Default")
      (node (ref "IC5") (pin "10") (pinfunction "PGND3_10") (pintype "power_in"))
      (node (ref "IC5") (pin "12") (pinfunction "COMPP_12") (pintype "input"))
      (node (ref "IC5") (pin "6") (pinfunction "PGND1_6") (pintype "power_in"))
      (node (ref "IC5") (pin "7") (pinfunction "PGND2_7") (pintype "power_in"))
      (node (ref "R7-1") (pin "2") (pinfunction "2_2") (pintype "passive"))
    )
    (net (code "62") (name "Net-(IC5-CPH)") (class "Default")
      (node (ref "C7-1") (pin "2") (pinfunction "2_2") (pintype "passive"))
      (node (ref "IC5") (pin "2") (pinfunction "CPH_2") (pintype "power_in"))
    )
    (net (code "63") (name "Net-(IC5-CPL)") (class "Default")
      (node (ref "C7-1") (pin "1") (pinfunction "1_1") (pintype "passive"))
      (node (ref "IC5") (pin "1") (pinfunction "CPL_1") (pintype "power_in"))
    )
    (net (code "64") (name "Net-(IC5-V3P3)") (class "Default")
      (node (ref "IC5") (pin "15") (pinfunction "V3P3_15") (pintype "power_in"))
      (node (ref "TR7-1") (pin "2") (pinfunction "E_2") (pintype "passive"))
    )
    (net (code "65") (name "Net-(IC5-VCP)") (class "Default")
      (node (ref "C7-2") (pin "1") (pinfunction "1_1") (pintype "passive"))
      (node (ref "IC5") (pin "3") (pinfunction "VCP_3") (pintype "power_in"))
    )
    (net (code "66") (name "Net-(IC6-COMPN)") (class "Default")
      (node (ref "IC6") (pin "13") (pinfunction "COMPN_13") (pintype "input"))
      (node (ref "ILIM3") (pin "TP") (pinfunction "TP_TP") (pintype "input"))
      (node (ref "TR8-1") (pin "3") (pinfunction "S_3") (pintype "passive"))
    )
    (net (code "67") (name "Net-(IC6-COMPP)") (class "Default")
      (node (ref "IC6") (pin "10") (pinfunction "PGND3_10") (pintype "power_in"))
      (node (ref "IC6") (pin "12") (pinfunction "COMPP_12") (pintype "input"))
      (node (ref "IC6") (pin "6") (pinfunction "PGND1_6") (pintype "power_in"))
      (node (ref "IC6") (pin "7") (pinfunction "PGND2_7") (pintype "power_in"))
      (node (ref "R8-1") (pin "2") (pinfunction "2_2") (pintype "passive"))
    )
    (net (code "68") (name "Net-(IC6-CPH)") (class "Default")
      (node (ref "C8-1") (pin "2") (pinfunction "2_2") (pintype "passive"))
      (node (ref "IC6") (pin "2") (pinfunction "CPH_2") (pintype "power_in"))
    )
    (net (code "69") (name "Net-(IC6-CPL)") (class "Default")
      (node (ref "C8-1") (pin "1") (pinfunction "1_1") (pintype "passive"))
      (node (ref "IC6") (pin "1") (pinfunction "CPL_1") (pintype "power_in"))
    )
    (net (code "70") (name "Net-(IC6-V3P3)") (class "Default")
      (node (ref "IC6") (pin "15") (pinfunction "V3P3_15") (pintype "power_in"))
      (node (ref "TR8-1") (pin "2") (pinfunction "E_2") (pintype "passive"))
    )
    (net (code "71") (name "Net-(IC6-VCP)") (class "Default")
      (node (ref "C8-2") (pin "1") (pinfunction "1_1") (pintype "passive"))
      (node (ref "IC6") (pin "3") (pinfunction "VCP_3") (pintype "power_in"))
    )
    (net (code "72") (name "Net-(L029-PadC)") (class "Default")
      (node (ref "L029") (pin "C") (pinfunction "C_C") (pintype "passive"))
      (node (ref "R5-1") (pin "2") (pinfunction "2_2") (pintype "passive"))
    )
    (net (code "73") (name "Net-(LED3-1-PadC)") (class "Default")
      (node (ref "LED3-1") (pin "C") (pinfunction "C_C") (pintype "passive"))
      (node (ref "R3-1") (pin "2") (pinfunction "2_2") (pintype "passive"))
    )
    (net (code "74") (name "unconnected-(IC1-RTCXOUT-Pad32)") (class "Default")
      (node (ref "IC1") (pin "32") (pinfunction "RTCXOUT_32") (pintype "bidirectional"))
    )
    (net (code "75") (name "unconnected-(IC2-NC-Pad21)") (class "Default")
      (node (ref "IC2") (pin "21") (pinfunction "NC_21") (pintype "no_connect"))
    )
    (net (code "76") (name "unconnected-(IC2-NCOMPO-Pad19)") (class "Default")
      (node (ref "IC2") (pin "19") (pinfunction "NCOMPO_19") (pintype "output"))
    )
    (net (code "77") (name "unconnected-(IC2-NFAULT-Pad18)") (class "Default")
      (node (ref "IC2") (pin "18") (pinfunction "NFAULT_18") (pintype "output"))
    )
    (net (code "78") (name "unconnected-(IC2-NRESET-Pad16)") (class "Default")
      (node (ref "IC2") (pin "16") (pinfunction "NRESET_16") (pintype "bidirectional"))
    )
    (net (code "79") (name "unconnected-(IC2-NSLEEP-Pad17)") (class "Default")
      (node (ref "IC2") (pin "17") (pinfunction "NSLEEP_17") (pintype "bidirectional"))
    )
    (net (code "80") (name "unconnected-(IC3-CBUS0-Pad18)") (class "Default")
      (node (ref "IC3") (pin "18") (pinfunction "CBUS0_18") (pintype "bidirectional"))
    )
    (net (code "81") (name "unconnected-(IC3-CBUS1-Pad17)") (class "Default")
      (node (ref "IC3") (pin "17") (pinfunction "CBUS1_17") (pintype "bidirectional"))
    )
    (net (code "82") (name "unconnected-(IC3-CBUS2-Pad10)") (class "Default")
      (node (ref "IC3") (pin "10") (pinfunction "CBUS2_10") (pintype "bidirectional"))
    )
    (net (code "83") (name "unconnected-(IC3-CBUS3-Pad19)") (class "Default")
      (node (ref "IC3") (pin "19") (pinfunction "CBUS3_19") (pintype "bidirectional"))
    )
    (net (code "84") (name "unconnected-(IC3-CTS#-Pad9)") (class "Default")
      (node (ref "IC3") (pin "9") (pinfunction "CTS#_9") (pintype "bidirectional"))
    )
    (net (code "85") (name "unconnected-(IC3-DCD#-Pad8)") (class "Default")
      (node (ref "IC3") (pin "8") (pinfunction "DCD#_8") (pintype "bidirectional"))
    )
    (net (code "86") (name "unconnected-(IC3-DSR#-Pad7)") (class "Default")
      (node (ref "IC3") (pin "7") (pinfunction "DSR#_7") (pintype "bidirectional"))
    )
    (net (code "87") (name "unconnected-(IC3-DTR#-Pad1)") (class "Default")
      (node (ref "IC3") (pin "1") (pinfunction "DTR#_1") (pintype "output"))
    )
    (net (code "88") (name "unconnected-(IC3-RI#-Pad5)") (class "Default")
      (node (ref "IC3") (pin "5") (pinfunction "RI#_5") (pintype "bidirectional"))
    )
    (net (code "89") (name "unconnected-(IC3-RTS#-Pad2)") (class "Default")
      (node (ref "IC3") (pin "2") (pinfunction "RTS#_2") (pintype "output"))
    )
    (net (code "90") (name "unconnected-(IC5-NC-Pad21)") (class "Default")
      (node (ref "IC5") (pin "21") (pinfunction "NC_21") (pintype "no_connect"))
    )
    (net (code "91") (name "unconnected-(IC5-NCOMPO-Pad19)") (class "Default")
      (node (ref "IC5") (pin "19") (pinfunction "NCOMPO_19") (pintype "output"))
    )
    (net (code "92") (name "unconnected-(IC5-NFAULT-Pad18)") (class "Default")
      (node (ref "IC5") (pin "18") (pinfunction "NFAULT_18") (pintype "output"))
    )
    (net (code "93") (name "unconnected-(IC5-NRESET-Pad16)") (class "Default")
      (node (ref "IC5") (pin "16") (pinfunction "NRESET_16") (pintype "bidirectional"))
    )
    (net (code "94") (name "unconnected-(IC5-NSLEEP-Pad17)") (class "Default")
      (node (ref "IC5") (pin "17") (pinfunction "NSLEEP_17") (pintype "bidirectional"))
    )
    (net (code "95") (name "unconnected-(IC6-NC-Pad21)") (class "Default")
      (node (ref "IC6") (pin "21") (pinfunction "NC_21") (pintype "no_connect"))
    )
    (net (code "96") (name "unconnected-(IC6-NCOMPO-Pad19)") (class "Default")
      (node (ref "IC6") (pin "19") (pinfunction "NCOMPO_19") (pintype "output"))
    )
    (net (code "97") (name "unconnected-(IC6-NFAULT-Pad18)") (class "Default")
      (node (ref "IC6") (pin "18") (pinfunction "NFAULT_18") (pintype "output"))
    )
    (net (code "98") (name "unconnected-(IC6-NRESET-Pad16)") (class "Default")
      (node (ref "IC6") (pin "16") (pinfunction "NRESET_16") (pintype "bidirectional"))
    )
    (net (code "99") (name "unconnected-(IC6-NSLEEP-Pad17)") (class "Default")
      (node (ref "IC6") (pin "17") (pinfunction "NSLEEP_17") (pintype "bidirectional"))
    )
    (net (code "100") (name "unconnected-(ISP-Pad3)") (class "Default")
      (node (ref "ISP") (pin "3") (pinfunction "3_3") (pintype "passive"))
    )
    (net (code "101") (name "unconnected-(SWD-Pad1)") (class "Default")
      (node (ref "SWD") (pin "1") (pinfunction "1_1") (pintype "passive"))
    )
    (net (code "102") (name "unconnected-(USB-ID-Pad4)") (class "Default")
      (node (ref "USB") (pin "4") (pinfunction "ID_4") (pintype "bidirectional"))
    )
  )
)
